# 30to50V-24V_10A_1.net
KiCad netlist of a schematic drawn in Altium Designer
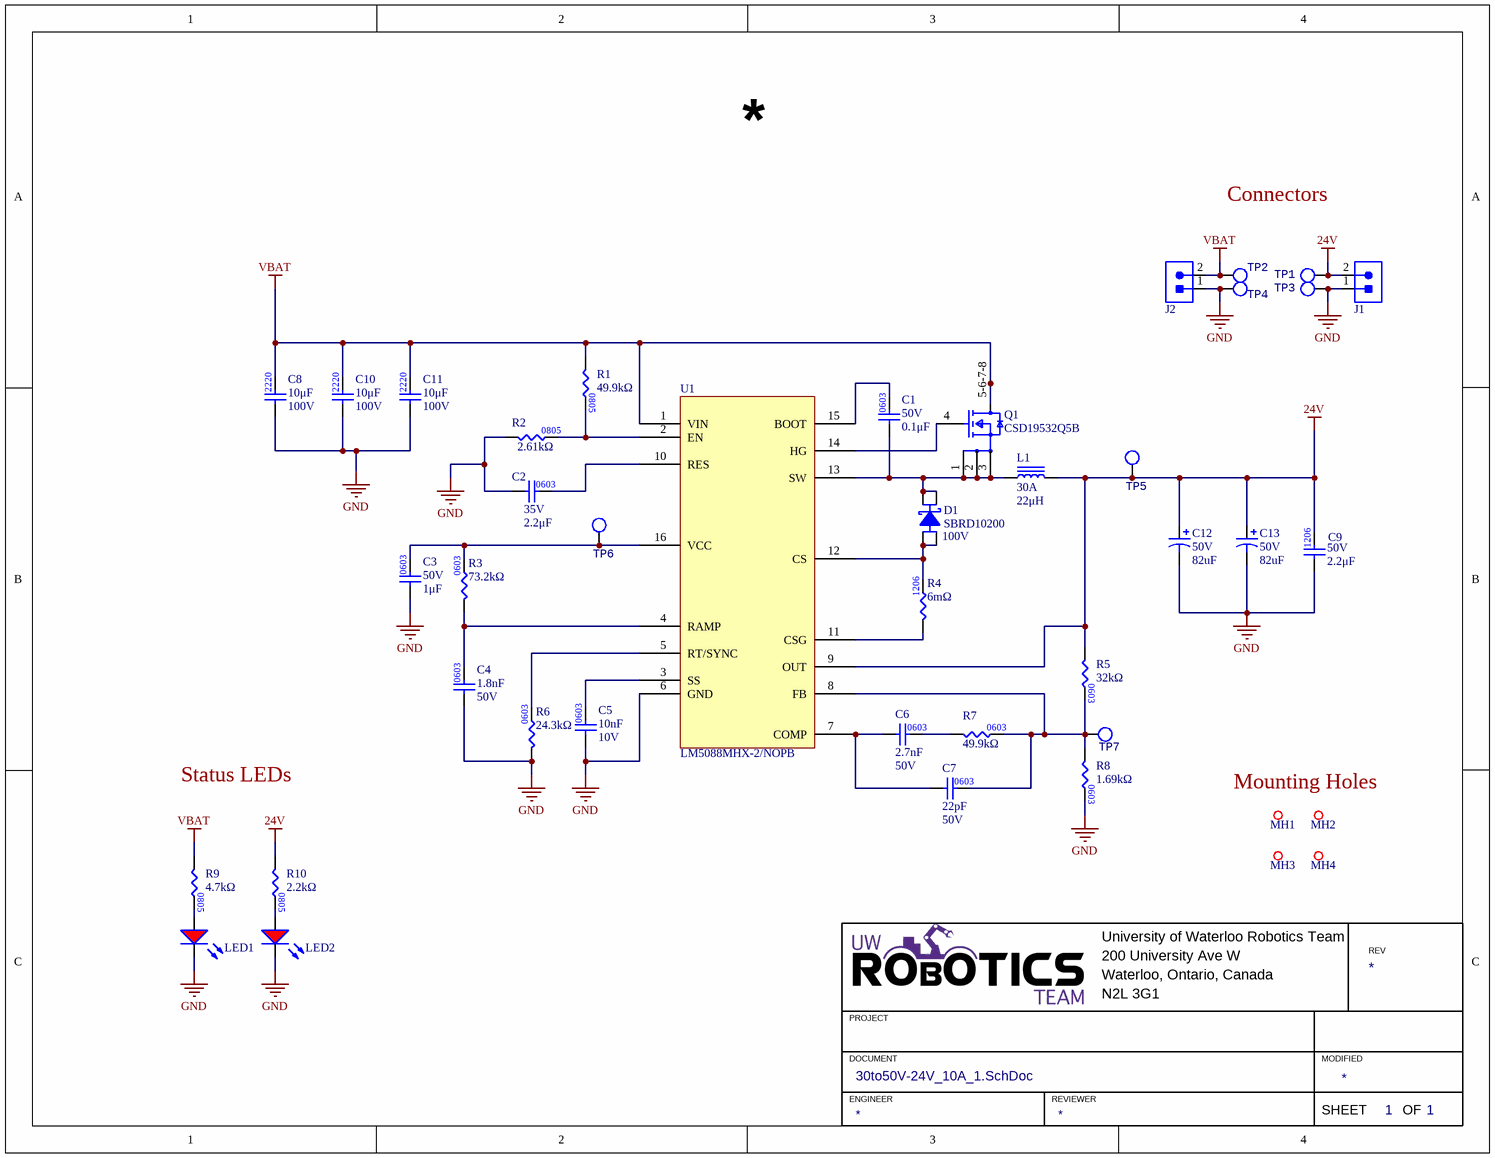
[diagram p0: 30to50V-24V_10A_1.SchDoc]

(export (version "E")
  (design (tool "Eeschema 10.0.6"))
  (components
    (comp (ref "C1")
      (value "0.1μF")
      (footprint "CAP0603")
      (description "CAP CER 0.1UF 50V X7R 0603")
      (fields (field (name "VOLTAGE RATING") "50V") (field (name "Comment") "CAP_0.1uF_50V_0603"))
      (libsource (lib "UWRT_Schematic_Library_2020") (part "CAP_0.1uF_50V_0603"))
    )
    (comp (ref "C2")
      (value "2.2μF")
      (footprint "CAP0603")
      (description "CAP CER 2.2UF 35V X5R 0603")
      (fields (field (name "VOLTAGE RATING") "35V") (field (name "Comment") "CAP_2.2uF_35V_0603"))
      (libsource (lib "UWRT_Schematic_Library_2020") (part "CAP_2.2uF_35V_0603"))
    )
    (comp (ref "C3")
      (value "1μF")
      (footprint "CAP0603")
      (description "CAP CER 1UF 50V X6S 0603")
      (fields (field (name "VOLTAGE RATING") "50V") (field (name "Comment") "CAP_1uF_50V_0603"))
      (libsource (lib "UWRT_Schematic_Library_2020") (part "CAP_1uF_50V_0603"))
    )
    (comp (ref "C4")
      (value "1.8nF")
      (footprint "CAP0603")
      (description "CAP CER 1800PF 50V C0G/NP0 0603")
      (fields (field (name "VOLTAGE RATING") "50V") (field (name "Comment") "CAP_1.8nF_50V_0603"))
      (libsource (lib "UWRT_Schematic_Library_2020") (part "CAP_1.8nF_50V_0603"))
    )
    (comp (ref "C5")
      (value "10nF")
      (footprint "CAP0603")
      (description "CAP CER 10000PF 25V C0G 0603")
      (fields (field (name "VOLTAGE RATING") "10V") (field (name "Comment") "CAP_10nF_25V_0603"))
      (libsource (lib "UWRT_Schematic_Library_2020") (part "CAP_10nF_25V_0603"))
    )
    (comp (ref "C6")
      (value "2.7nF")
      (footprint "CAP0603")
      (description "CAP CER 2700PF 50V X7R 0603")
      (fields (field (name "VOLTAGE RATING") "50V") (field (name "Comment") "CAP_2.7nF_50V_0603"))
      (libsource (lib "UWRT_Schematic_Library_2020") (part "CAP_2.7nF_50V_0603"))
    )
    (comp (ref "C7")
      (value "22pF")
      (footprint "CAP0603")
      (description "CAP CER 22PF 50V C0G/NPO 0603")
      (fields (field (name "VOLTAGE RATING") "50V") (field (name "Comment") "CAP_22pF_50V_0603"))
      (libsource (lib "UWRT_Schematic_Library_2020") (part "CAP_22pF_50V_0603"))
    )
    (comp (ref "C8")
      (value "10μF")
      (footprint "C5750X7S2A106M230KB")
      (description "CAP CER 10UF 100V X7S 2220")
      (fields (field (name "VOLTAGE RATING") "100V") (field (name "Comment") "CAP_10uF_50V_2220"))
      (libsource (lib "UWRT_Schematic_Library_2020") (part "CAP_10uF_50V_2220"))
    )
    (comp (ref "C9")
      (value "2.2μF")
      (footprint "CAP1206")
      (description "CAP CER 2.2UF 50V X7R 1206")
      (fields (field (name "VOLTAGE RATING") "50V") (field (name "Comment") "CAP_2.2uF_50V_1206"))
      (libsource (lib "UWRT_Schematic_Library_2020") (part "CAP_2.2uF_50V_1206"))
    )
    (comp (ref "C10")
      (value "10μF")
      (footprint "C5750X7S2A106M230KB")
      (description "CAP CER 10UF 100V X7S 2220")
      (fields (field (name "VOLTAGE RATING") "100V") (field (name "Comment") "CAP_10uF_50V_2220"))
      (libsource (lib "UWRT_Schematic_Library_2020") (part "CAP_10uF_50V_2220"))
    )
    (comp (ref "C11")
      (value "10μF")
      (footprint "C5750X7S2A106M230KB")
      (description "CAP CER 10UF 100V X7S 2220")
      (fields (field (name "VOLTAGE RATING") "100V") (field (name "Comment") "CAP_10uF_50V_2220"))
      (libsource (lib "UWRT_Schematic_Library_2020") (part "CAP_10uF_50V_2220"))
    )
    (comp (ref "C12")
      (value "CAP_47uF_100V_ALUM")
      (footprint "RADIAL_CORNELL_D")
      (fields
        (field (name "MANUFACTURER") "Nichicon")
        (field (name "MANUFACTURER PART NUMBER") "UCD2A470MNQ1MS")
        (field (name "VOLTAGE RATING") "50V")
        (field (name "CAPACITANCE") "82uF")
      )
      (libsource (lib "UWRT_Schematic_Library_2020") (part "CAP_47uF_100V_ALUM"))
    )
    (comp (ref "C13")
      (value "CAP_47uF_100V_ALUM")
      (footprint "RADIAL_CORNELL_D")
      (fields
        (field (name "MANUFACTURER") "Nichicon")
        (field (name "MANUFACTURER PART NUMBER") "UCD2A470MNQ1MS")
        (field (name "VOLTAGE RATING") "50V")
        (field (name "CAPACITANCE") "82uF")
      )
      (libsource (lib "UWRT_Schematic_Library_2020") (part "CAP_47uF_100V_ALUM"))
    )
    (comp (ref "D1")
      (value "DIO_SCHOTTKY_100V_5.5A")
      (footprint "D-PAK")
      (description "DIODE SCHOTTKY 200V 10A DPAK")
      (fields (field (name "MANUFACTURER PART NUMBER 1") "SBRD10200") (field (name "VR (MAX)") "100V"))
      (libsource (lib "UWRT_Schematic_Library_2020") (part "DIO_SCHOTTKY_200V_10A"))
    )
    (comp (ref "J1")
      (value "CON_2POS_SCREW_TERM")
      (footprint "1935161")
      (description "TERM BLK 2POS SIDE ENTRY 5MM")
      (libsource (lib "UWRT_Schematic_Library_2020") (part "CON_2POS_SCREW_TERM"))
    )
    (comp (ref "J2")
      (value "CON_2POS_SCREW_TERM")
      (footprint "1935161")
      (description "TERM BLK 2POS SIDE ENTRY 5MM")
      (libsource (lib "") (part "CON_2POS_SCREW_TERM_1"))
    )
    (comp (ref "L1")
      (value "IND_22uH_30A")
      (footprint "IND_VISHAY_IHLP6767GZ51")
      (description "FIXED IND 22UH 30A 2.4 MOHM SMD")
      (fields (field (name "CURRENT RATING") "30A") (field (name "INDUCTANCE") "22μH"))
      (libsource (lib "UWRT_Schematic_Library_2020") (part "IND_22uH_30A"))
    )
    (comp (ref "LED1")
      (value "LED_RED")
      (footprint "LED_0805_RED")
      (description "LED RED DIFFUSED 0805 SMD")
      (libsource (lib "UWRT_Schematic_Library_2020") (part "LED_RED"))
    )
    (comp (ref "LED2")
      (value "LED_RED")
      (footprint "LED_0805_RED")
      (description "LED RED DIFFUSED 0805 SMD")
      (libsource (lib "UWRT_Schematic_Library_2020") (part "LED_RED"))
    )
    (comp (ref "MH1")
      (value "MOUNTING_HOLE_M3_GIMBAL_REV2")
      (footprint "MOUNTING_HOLE_3mm_GIMBAL_REV2")
      (description "MOUNTING_HOLE_M3 Gimbal Rev2")
      (libsource (lib "UWRT_Schematic_Library_2020") (part "MOUNTING_HOLE_M3_GIMBAL_REV2"))
    )
    (comp (ref "MH2")
      (value "MOUNTING_HOLE_M3_GIMBAL_REV2")
      (footprint "MOUNTING_HOLE_3mm_GIMBAL_REV2")
      (description "MOUNTING_HOLE_M3 Gimbal Rev2")
      (libsource (lib "UWRT_Schematic_Library_2020") (part "MOUNTING_HOLE_M3_GIMBAL_REV2"))
    )
    (comp (ref "MH3")
      (value "MOUNTING_HOLE_M3_GIMBAL_REV2")
      (footprint "MOUNTING_HOLE_3mm_GIMBAL_REV2")
      (description "MOUNTING_HOLE_M3 Gimbal Rev2")
      (libsource (lib "UWRT_Schematic_Library_2020") (part "MOUNTING_HOLE_M3_GIMBAL_REV2"))
    )
    (comp (ref "MH4")
      (value "MOUNTING_HOLE_M3_GIMBAL_REV2")
      (footprint "MOUNTING_HOLE_3mm_GIMBAL_REV2")
      (description "MOUNTING_HOLE_M3 Gimbal Rev2")
      (libsource (lib "UWRT_Schematic_Library_2020") (part "MOUNTING_HOLE_M3_GIMBAL_REV2"))
    )
    (comp (ref "Q1")
      (value "CSD19532Q5B")
      (footprint "FP-DNK0008A-MFG")
      (description "MOSFET N-CH 100V 100A 8SON")
      (fields
        (field (name "OCTOPART") "https://octopart.com/csd19532q5b-texas+instruments-32890191")
        (field (name "MANUFACTURER") "Texas Instruments")
      )
      (libsource (lib "Components - 13.07.23 - 19.12") (part "CMP-04962-000007-1"))
    )
    (comp (ref "R1")
      (value "49.9kΩ")
      (footprint "RES0805")
      (description "RES 49.9K OHM 1% 1/8W 0805")
      (fields (field (name "LCSC PART #") "C17719") (field (name "Comment") "RES_49.9kΩ_0805_1%"))
      (libsource (lib "UWRT_Schematic_Library_2020") (part "RES_49.9kΩ_0805_1%"))
    )
    (comp (ref "R2")
      (value "2.61kΩ")
      (footprint "RES0805")
      (description "RES 2.61K OHM 1% 1/8W 0805")
      (fields (field (name "Comment") "RES_2.61kΩ_0805_1%"))
      (libsource (lib "UWRT_Schematic_Library_2020") (part "RES_2.61kΩ_0805_1%"))
    )
    (comp (ref "R3")
      (value "73.2kΩ")
      (footprint "RES0603")
      (description "RES 73.2K OHM 1% 1/10W 0603")
      (fields (field (name "POWER") "0.1W") (field (name "TOLERANCE") "1%"))
      (libsource (lib "UWRT_Schematic_Library_2020") (part "RES_73.2kΩ_0603_1%"))
    )
    (comp (ref "R4")
      (value "6mΩ")
      (footprint "RES1206")
      (description "RES 0.006 OHM 1% 1W 1206")
      (fields (field (name "Comment") "RES_0.006Ω_1206_1%"))
      (libsource (lib "UWRT_Schematic_Library_2020") (part "RES_0.006Ω_1206_1%"))
    )
    (comp (ref "R5")
      (value "32kΩ")
      (footprint "RES0603")
      (description "RES SMD 32K OHM 0.1% 1/10W 0603")
      (fields (field (name "Comment") "RES_32KΩ_0603_0.1%"))
      (libsource (lib "UWRT_Schematic_Library_2020") (part "RES_32KΩ_0603_0.1%"))
    )
    (comp (ref "R6")
      (value "24.3kΩ")
      (footprint "RES0603")
      (description "RES 24.3K OHM 1% 1/10W 0603")
      (fields (field (name "POWER") "0.1W") (field (name "TOLERANCE") "1%"))
      (libsource (lib "UWRT_Schematic_Library_2020") (part "RES_24.3kΩ_0603_1%"))
    )
    (comp (ref "R7")
      (value "49.9kΩ")
      (footprint "RES0603")
      (description "RES 49.9K OHM 1% 1/10W 0603")
      (fields (field (name "Comment") "RES_49.9kΩ_0603_1%"))
      (libsource (lib "UWRT_Schematic_Library_2020") (part "RES_49.9kΩ_0603_1%"))
    )
    (comp (ref "R8")
      (value "1.69kΩ")
      (footprint "RES0603")
      (description "RES 1.69K OHM 1% 1/10W 0603")
      (fields (field (name "Comment") "RES_1.69kΩ_0603_1%"))
      (libsource (lib "UWRT_Schematic_Library_2020") (part "RES_1.69kΩ_0603_1%"))
    )
    (comp (ref "R9")
      (value "4.7kΩ")
      (footprint "RES0805")
      (description "RES 4.7K OHM 5% 1/8W 0805")
      (fields (field (name "LCSC PART #") "C17673") (field (name "Comment") "RES_4.7kΩ_0805_5%"))
      (libsource (lib "UWRT_Schematic_Library_2020") (part "RES_4.7kΩ_0805_5%"))
    )
    (comp (ref "R10")
      (value "2.2kΩ")
      (footprint "RES0805")
      (description "RES 2.2K OHM 5% 1/8W 0805")
      (fields (field (name "TOLERANCE") "5%") (field (name "Comment") "RES_2.2kΩ_0805_5%"))
      (libsource (lib "UWRT_Schematic_Library_2020") (part "RES_2.2kΩ_0805_5%"))
    )
    (comp (ref "TP1")
      (value "TESTPOINT_LOOP")
      (footprint "TESTPOINT_LOOP")
      (description "TESTPOINT THRUHOLE")
      (libsource (lib "UWRT_Schematic_Library_2020") (part "TESTPOINT_LOOP"))
    )
    (comp (ref "TP2")
      (value "TESTPOINT_LOOP")
      (footprint "TESTPOINT_LOOP")
      (description "TESTPOINT THRUHOLE")
      (libsource (lib "UWRT_Schematic_Library_2020") (part "TESTPOINT_LOOP"))
    )
    (comp (ref "TP3")
      (value "TESTPOINT_LOOP")
      (footprint "TESTPOINT_LOOP")
      (description "TESTPOINT THRUHOLE")
      (libsource (lib "UWRT_Schematic_Library_2020") (part "TESTPOINT_LOOP"))
    )
    (comp (ref "TP4")
      (value "TESTPOINT_LOOP")
      (footprint "TESTPOINT_LOOP")
      (description "TESTPOINT THRUHOLE")
      (libsource (lib "UWRT_Schematic_Library_2020") (part "TESTPOINT_LOOP"))
    )
    (comp (ref "TP5")
      (value "TESTPOINT_LOOP")
      (footprint "TESTPOINT_LOOP")
      (description "TESTPOINT THRUHOLE")
      (libsource (lib "UWRT_Schematic_Library_2020") (part "TESTPOINT_LOOP"))
    )
    (comp (ref "TP6")
      (value "TESTPOINT_LOOP")
      (footprint "TESTPOINT_LOOP")
      (description "TESTPOINT THRUHOLE")
      (libsource (lib "UWRT_Schematic_Library_2020") (part "TESTPOINT_LOOP"))
    )
    (comp (ref "TP7")
      (value "TESTPOINT_LOOP")
      (footprint "TESTPOINT_LOOP")
      (description "TESTPOINT THRUHOLE")
      (libsource (lib "UWRT_Schematic_Library_2020") (part "TESTPOINT_LOOP"))
    )
    (comp (ref "U1")
      (value "LM5088")
      (description "IC REG CTRLR BUCK 16HTSSOP")
      (fields (field (name "MANUFACTURER PART NUMBER 1") "LM5088MHX-2/NOPB"))
      (libsource (lib "UWRT_Schematic_Library_2020") (part "LM5088MHX-2/NOPB"))
    )
  )
  (nets
    (net (code "1") (name "24V") (class "Default")
      (node (ref "C12") (pin "1") (pinfunction "1_1") (pintype "passive"))
      (node (ref "C13") (pin "1") (pinfunction "1_1") (pintype "passive"))
      (node (ref "C9") (pin "2") (pinfunction "2_2") (pintype "passive"))
      (node (ref "J1") (pin "2") (pinfunction "2_2") (pintype "passive"))
      (node (ref "L1") (pin "2") (pinfunction "2_2") (pintype "passive"))
      (node (ref "R10") (pin "1") (pinfunction "1_1") (pintype "passive"))
      (node (ref "R5") (pin "1") (pinfunction "1_1") (pintype "passive"))
      (node (ref "TP1") (pin "1") (pintype "passive"))
      (node (ref "TP5") (pin "1") (pintype "passive"))
      (node (ref "U1") (pin "9") (pinfunction "OUT_9") (pintype "passive"))
    )
    (net (code "2") (name "GND") (class "Default")
      (node (ref "C10") (pin "1") (pinfunction "1_1") (pintype "passive"))
      (node (ref "C11") (pin "1") (pinfunction "1_1") (pintype "passive"))
      (node (ref "C12") (pin "2") (pinfunction "2_2") (pintype "passive"))
      (node (ref "C13") (pin "2") (pinfunction "2_2") (pintype "passive"))
      (node (ref "C2") (pin "1") (pinfunction "1_1") (pintype "passive"))
      (node (ref "C3") (pin "1") (pinfunction "1_1") (pintype "passive"))
      (node (ref "C4") (pin "1") (pinfunction "1_1") (pintype "passive"))
      (node (ref "C5") (pin "1") (pinfunction "1_1") (pintype "passive"))
      (node (ref "C8") (pin "1") (pinfunction "1_1") (pintype "passive"))
      (node (ref "C9") (pin "1") (pinfunction "1_1") (pintype "passive"))
      (node (ref "J1") (pin "1") (pinfunction "1_1") (pintype "passive"))
      (node (ref "J2") (pin "1") (pinfunction "1_1") (pintype "passive"))
      (node (ref "LED1") (pin "2") (pinfunction "K_2") (pintype "passive"))
      (node (ref "LED2") (pin "2") (pinfunction "K_2") (pintype "passive"))
      (node (ref "R2") (pin "1") (pinfunction "1_1") (pintype "passive"))
      (node (ref "R6") (pin "1") (pinfunction "1_1") (pintype "passive"))
      (node (ref "R8") (pin "2") (pinfunction "2_2") (pintype "passive"))
      (node (ref "TP3") (pin "1") (pintype "passive"))
      (node (ref "TP4") (pin "1") (pintype "passive"))
      (node (ref "U1") (pin "6") (pinfunction "GND_6") (pintype "passive"))
    )
    (net (code "3") (name "Net-(C6-Pad2)") (class "Default")
      (node (ref "C6") (pin "2") (pinfunction "2_2") (pintype "passive"))
      (node (ref "R7") (pin "1") (pinfunction "1_1") (pintype "passive"))
    )
    (net (code "4") (name "Net-(LED1-A)") (class "Default")
      (node (ref "LED1") (pin "1") (pinfunction "A_1") (pintype "passive"))
      (node (ref "R9") (pin "2") (pinfunction "2_2") (pintype "passive"))
    )
    (net (code "5") (name "Net-(LED2-A)") (class "Default")
      (node (ref "LED2") (pin "1") (pinfunction "A_1") (pintype "passive"))
      (node (ref "R10") (pin "2") (pinfunction "2_2") (pintype "passive"))
    )
    (net (code "6") (name "Net-(Q1-G)") (class "Default")
      (node (ref "Q1") (pin "4") (pinfunction "G_4") (pintype "passive"))
      (node (ref "U1") (pin "14") (pinfunction "HG_14") (pintype "passive"))
    )
    (net (code "7") (name "Net-(U1-BOOT)") (class "Default")
      (node (ref "C1") (pin "2") (pinfunction "2_2") (pintype "passive"))
      (node (ref "U1") (pin "15") (pinfunction "BOOT_15") (pintype "passive"))
    )
    (net (code "8") (name "Net-(U1-COMP)") (class "Default")
      (node (ref "C6") (pin "1") (pinfunction "1_1") (pintype "passive"))
      (node (ref "C7") (pin "1") (pinfunction "1_1") (pintype "passive"))
      (node (ref "U1") (pin "7") (pinfunction "COMP_7") (pintype "passive"))
    )
    (net (code "9") (name "Net-(U1-CS)") (class "Default")
      (node (ref "D1") (pin "1") (pinfunction "Anode_1") (pintype "passive"))
      (node (ref "D1") (pin "3") (pinfunction "Anode_3") (pintype "passive"))
      (node (ref "R4") (pin "2") (pinfunction "2_2") (pintype "passive"))
      (node (ref "U1") (pin "12") (pinfunction "CS_12") (pintype "passive"))
    )
    (net (code "10") (name "Net-(U1-CSG)") (class "Default")
      (node (ref "R4") (pin "1") (pinfunction "1_1") (pintype "passive"))
      (node (ref "U1") (pin "11") (pinfunction "CSG_11") (pintype "passive"))
    )
    (net (code "11") (name "Net-(U1-EN)") (class "Default")
      (node (ref "R1") (pin "2") (pinfunction "2_2") (pintype "passive"))
      (node (ref "R2") (pin "2") (pinfunction "2_2") (pintype "passive"))
      (node (ref "U1") (pin "2") (pinfunction "EN_2") (pintype "passive"))
    )
    (net (code "12") (name "Net-(U1-FB)") (class "Default")
      (node (ref "C7") (pin "2") (pinfunction "2_2") (pintype "passive"))
      (node (ref "R5") (pin "2") (pinfunction "2_2") (pintype "passive"))
      (node (ref "R7") (pin "2") (pinfunction "2_2") (pintype "passive"))
      (node (ref "R8") (pin "1") (pinfunction "1_1") (pintype "passive"))
      (node (ref "TP7") (pin "1") (pintype "passive"))
      (node (ref "U1") (pin "8") (pinfunction "FB_8") (pintype "passive"))
    )
    (net (code "13") (name "Net-(U1-RAMP)") (class "Default")
      (node (ref "C4") (pin "2") (pinfunction "2_2") (pintype "passive"))
      (node (ref "R3") (pin "1") (pinfunction "1_1") (pintype "passive"))
      (node (ref "U1") (pin "4") (pinfunction "RAMP_4") (pintype "passive"))
    )
    (net (code "14") (name "Net-(U1-RES)") (class "Default")
      (node (ref "C2") (pin "2") (pinfunction "2_2") (pintype "passive"))
      (node (ref "U1") (pin "10") (pinfunction "RES_10") (pintype "passive"))
    )
    (net (code "15") (name "Net-(U1-RT{slash}SYNC)") (class "Default")
      (node (ref "R6") (pin "2") (pinfunction "2_2") (pintype "passive"))
      (node (ref "U1") (pin "5") (pinfunction "RT/SYNC_5") (pintype "passive"))
    )
    (net (code "16") (name "Net-(U1-SS)") (class "Default")
      (node (ref "C5") (pin "2") (pinfunction "2_2") (pintype "passive"))
      (node (ref "U1") (pin "3") (pinfunction "SS_3") (pintype "passive"))
    )
    (net (code "17") (name "Net-(U1-SW)") (class "Default")
      (node (ref "C1") (pin "1") (pinfunction "1_1") (pintype "passive"))
      (node (ref "D1") (pin "2") (pinfunction "Cathode_2") (pintype "passive"))
      (node (ref "D1") (pin "4") (pinfunction "Cathode_4") (pintype "passive"))
      (node (ref "L1") (pin "1") (pinfunction "1_1") (pintype "passive"))
      (node (ref "Q1") (pin "1") (pinfunction "S_1") (pintype "passive"))
      (node (ref "Q1") (pin "2") (pinfunction "S_2") (pintype "passive"))
      (node (ref "Q1") (pin "3") (pinfunction "S_3") (pintype "passive"))
      (node (ref "U1") (pin "13") (pinfunction "SW_13") (pintype "passive"))
    )
    (net (code "18") (name "Net-(U1-VCC)") (class "Default")
      (node (ref "C3") (pin "2") (pinfunction "2_2") (pintype "passive"))
      (node (ref "R3") (pin "2") (pinfunction "2_2") (pintype "passive"))
      (node (ref "TP6") (pin "1") (pintype "passive"))
      (node (ref "U1") (pin "16") (pinfunction "VCC_16") (pintype "passive"))
    )
    (net (code "19") (name "VBAT") (class "Default")
      (node (ref "C10") (pin "2") (pinfunction "2_2") (pintype "passive"))
      (node (ref "C11") (pin "2") (pinfunction "2_2") (pintype "passive"))
      (node (ref "C8") (pin "2") (pinfunction "2_2") (pintype "passive"))
      (node (ref "J2") (pin "2") (pinfunction "2_2") (pintype "passive"))
      (node (ref "Q1") (pin "5-6-7-8") (pinfunction "D_5-6-7-8") (pintype "passive"))
      (node (ref "R1") (pin "1") (pinfunction "1_1") (pintype "passive"))
      (node (ref "R9") (pin "1") (pinfunction "1_1") (pintype "passive"))
      (node (ref "TP2") (pin "1") (pintype "passive"))
      (node (ref "U1") (pin "1") (pinfunction "VIN_1") (pintype "passive"))
    )
  )
)
